# JLink-OB-072-Wiki-A1.net
KiCad netlist of a schematic drawn in Altium Designer
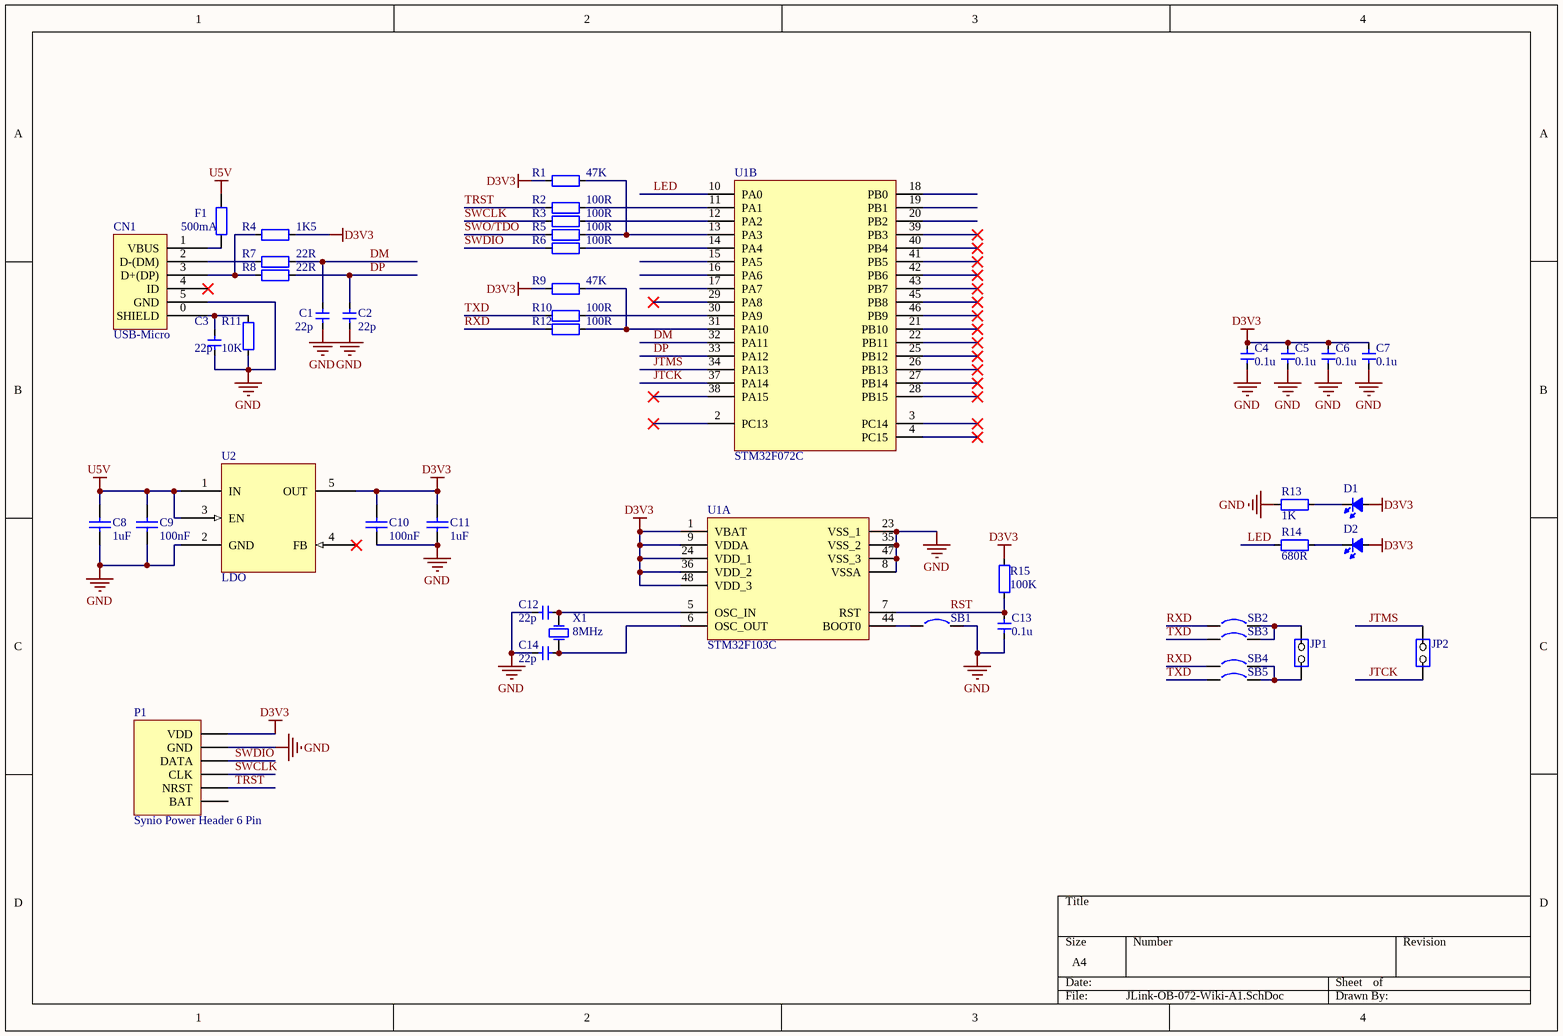
[diagram p0: JLink-OB-072-Wiki-A1.SchDoc]

(export (version "E")
  (design (tool "Eeschema 10.0.6"))
  (components
    (comp (ref "C1")
      (value "22p")
      (footprint "0603C")
      (description "Capacitor")
      (fields (field (name "Comment") "Cap_0603"))
      (libsource (lib "altium-import") (part "root_1_Cap_0603_"))
    )
    (comp (ref "C2")
      (value "22p")
      (footprint "0603C")
      (description "Capacitor")
      (fields (field (name "Comment") "Cap_0603"))
      (libsource (lib "SCH_Passive") (part "Cap_0603"))
    )
    (comp (ref "C3")
      (value "22p")
      (footprint "0603C")
      (description "Capacitor")
      (fields (field (name "Comment") "Cap_0603"))
      (libsource (lib "SCH_Passive") (part "Cap_0603"))
    )
    (comp (ref "C4")
      (value "0.1u")
      (footprint "0603C")
      (description "Capacitor")
      (fields (field (name "Comment") "Cap_0603"))
      (libsource (lib "SCH_Passive") (part "Cap_0603"))
    )
    (comp (ref "C5")
      (value "0.1u")
      (footprint "0603C")
      (description "Capacitor")
      (fields (field (name "Comment") "Cap_0603"))
      (libsource (lib "SCH_Passive") (part "Cap_0603"))
    )
    (comp (ref "C6")
      (value "0.1u")
      (footprint "0603C")
      (description "Capacitor")
      (fields (field (name "Comment") "Cap_0603"))
      (libsource (lib "SCH_Passive") (part "Cap_0603"))
    )
    (comp (ref "C7")
      (value "0.1u")
      (footprint "0603C")
      (description "Capacitor")
      (fields (field (name "Comment") "Cap_0603"))
      (libsource (lib "SCH_Passive") (part "Cap_0603"))
    )
    (comp (ref "C8")
      (value "1uF")
      (footprint "0603C")
      (description "Capacitor 0402 / 0603 / 0805")
      (libsource (lib "MCD_TOOLS") (part "Capacitor_ST"))
    )
    (comp (ref "C9")
      (value "100nF")
      (footprint "0603C")
      (description "Capacitor 0402 / 0603 / 0805")
      (libsource (lib "MCD_TOOLS") (part "Capacitor_ST"))
    )
    (comp (ref "C10")
      (value "100nF")
      (footprint "0603C")
      (description "Capacitor 0402 / 0603 / 0805")
      (libsource (lib "MCD_TOOLS") (part "Capacitor_ST"))
    )
    (comp (ref "C11")
      (value "1uF")
      (footprint "0603C")
      (description "Capacitor 0402 / 0603 / 0805")
      (libsource (lib "MCD_TOOLS") (part "Capacitor_ST"))
    )
    (comp (ref "C12")
      (value "22p")
      (footprint "0603C")
      (description "Capacitor")
      (fields (field (name "Comment") "Cap_0603"))
      (libsource (lib "SCH_Passive") (part "Cap_0603"))
    )
    (comp (ref "C13")
      (value "0.1u")
      (footprint "0603C")
      (description "Capacitor")
      (fields (field (name "Comment") "Cap_0603"))
      (libsource (lib "SCH_Passive") (part "Cap_0603"))
    )
    (comp (ref "C14")
      (value "22p")
      (footprint "0603C")
      (description "Capacitor")
      (fields (field (name "Comment") "Cap_0603"))
      (libsource (lib "SCH_Passive") (part "Cap_0603"))
    )
    (comp (ref "CN1")
      (value "USB-Micro")
      (footprint "USB_MICRO_5S_B")
      (libsource (lib "USB") (part "USB-Micro"))
    )
    (comp (ref "D1")
      (value "LED_0603")
      (footprint "LED-0603")
      (description "LED")
      (libsource (lib "SCH_Active") (part "LED_0603"))
    )
    (comp (ref "D2")
      (value "LED_0603")
      (footprint "LED-0603")
      (description "LED")
      (libsource (lib "SCH_Active") (part "LED_0603"))
    )
    (comp (ref "F1")
      (value "500mA")
      (footprint "0805M")
      (description "Resistor")
      (fields (field (name "PUBLISHER") "Altium Limited"))
      (libsource (lib "Misc") (part "Res"))
    )
    (comp (ref "JP1") (value "JP2") (footprint "HDR1X2/2.54mm") (libsource (lib "Connector") (part "JP2")))
    (comp (ref "JP2") (value "JP2") (footprint "HDR1X2/2.54mm") (libsource (lib "Connector") (part "JP2")))
    (comp (ref "P1")
      (value "Synio Power Header 6 Pin")
      (footprint "HDR1X6/2.54MM")
      (libsource (lib "Connector") (part "Synio Power Header 6 Pin"))
    )
    (comp (ref "R1")
      (value "47K")
      (footprint "0603R")
      (description "Resistor")
      (fields (field (name "Comment") "Res_0603"))
      (libsource (lib "") (part "Res_0603_1"))
    )
    (comp (ref "R2")
      (value "100R")
      (footprint "0603R")
      (description "Resistor")
      (fields (field (name "Comment") "Res_0603"))
      (libsource (lib "altium-import") (part "root_0_Res_0603_"))
    )
    (comp (ref "R3")
      (value "100R")
      (footprint "0603R")
      (description "Resistor")
      (fields (field (name "Comment") "Res_0603"))
      (libsource (lib "SCH_Passive") (part "Res_0603"))
    )
    (comp (ref "R4")
      (value "1K5")
      (footprint "0603R")
      (description "Resistor")
      (fields (field (name "Comment") "Res_0603"))
      (libsource (lib "SCH_Passive") (part "Res_0603"))
    )
    (comp (ref "R5")
      (value "100R")
      (footprint "0603R")
      (description "Resistor")
      (fields (field (name "Comment") "Res_0603"))
      (libsource (lib "SCH_Passive") (part "Res_0603"))
    )
    (comp (ref "R6")
      (value "100R")
      (footprint "0603R")
      (description "Resistor")
      (fields (field (name "Comment") "Res_0603"))
      (libsource (lib "SCH_Passive") (part "Res_0603"))
    )
    (comp (ref "R7")
      (value "22R")
      (footprint "0603R")
      (description "Resistor")
      (fields (field (name "Comment") "Res_0603"))
      (libsource (lib "SCH_Passive") (part "Res_0603"))
    )
    (comp (ref "R8")
      (value "22R")
      (footprint "0603R")
      (description "Resistor")
      (fields (field (name "Comment") "Res_0603"))
      (libsource (lib "SCH_Passive") (part "Res_0603"))
    )
    (comp (ref "R9")
      (value "47K")
      (footprint "0603R")
      (description "Resistor")
      (fields (field (name "Comment") "Res_0603"))
      (libsource (lib "") (part "Res_0603_1"))
    )
    (comp (ref "R10")
      (value "100R")
      (footprint "0603R")
      (description "Resistor")
      (fields (field (name "Comment") "Res_0603"))
      (libsource (lib "SCH_Passive") (part "Res_0603"))
    )
    (comp (ref "R11")
      (value "10K")
      (footprint "0603R")
      (description "Resistor")
      (fields (field (name "Comment") "Res_0603"))
      (libsource (lib "") (part "Res_0603_2"))
    )
    (comp (ref "R12")
      (value "100R")
      (footprint "0603R")
      (description "Resistor")
      (fields (field (name "Comment") "Res_0603"))
      (libsource (lib "SCH_Passive") (part "Res_0603"))
    )
    (comp (ref "R13")
      (value "1K")
      (footprint "0603R")
      (description "Resistor")
      (fields (field (name "Comment") "Res_0603"))
      (libsource (lib "SCH_Passive") (part "Res_0603"))
    )
    (comp (ref "R14")
      (value "680R")
      (footprint "0603R")
      (description "Resistor")
      (fields (field (name "Comment") "Res_0603"))
      (libsource (lib "SCH_Passive") (part "Res_0603"))
    )
    (comp (ref "R15")
      (value "100K")
      (footprint "0603R")
      (description "Resistor")
      (fields (field (name "Comment") "Res_0603"))
      (libsource (lib "") (part "Res_0603_2"))
    )
    (comp (ref "SB1")
      (value "Circuit Breaker")
      (footprint "JP2_SMD")
      (fields (field (name "PUBLISHER") "Altium Limited"))
      (libsource (lib "Misc") (part "Circuit Breaker"))
    )
    (comp (ref "SB2")
      (value "Circuit Breaker")
      (footprint "JP2_SMD")
      (fields (field (name "PUBLISHER") "Altium Limited"))
      (libsource (lib "Misc") (part "Circuit Breaker"))
    )
    (comp (ref "SB3")
      (value "Circuit Breaker")
      (footprint "JP2_SMD")
      (fields (field (name "PUBLISHER") "Altium Limited"))
      (libsource (lib "Misc") (part "Circuit Breaker"))
    )
    (comp (ref "SB4")
      (value "Circuit Breaker")
      (footprint "JP2_SMD")
      (fields (field (name "PUBLISHER") "Altium Limited"))
      (libsource (lib "Misc") (part "Circuit Breaker"))
    )
    (comp (ref "SB5")
      (value "Circuit Breaker")
      (footprint "JP2_SMD")
      (fields (field (name "PUBLISHER") "Altium Limited"))
      (libsource (lib "Misc") (part "Circuit Breaker"))
    )
    (comp (ref "U1")
      (value "STM32F103C")
      (footprint "LQFP48_N")
      (description "MCU")
      (libsource (lib "SCH_IC") (part "STM32F103C"))
    )
    (comp (ref "U2")
      (value "LDO")
      (footprint "SOT23-5")
      (description "General LDO SOT23-5")
      (libsource (lib "Power") (part "LDO-SOT23-5"))
    )
    (comp (ref "X1")
      (value "8MHz")
      (footprint "XTAL")
      (description "Crystal Oscillator")
      (fields (field (name "Comment") "XTAL_5032_2P"))
      (libsource (lib "SCH_Oscillator") (part "XTAL_5032_2P"))
    )
  )
  (nets
    (net (code "1") (name "/DM") (class "Default")
      (node (ref "C1") (pin "2") (pinfunction "2_2") (pintype "passive"))
      (node (ref "R7") (pin "2") (pinfunction "2_2") (pintype "passive"))
      (node (ref "U1") (pin "32") (pinfunction "PA11_32") (pintype "passive"))
    )
    (net (code "2") (name "/DP") (class "Default")
      (node (ref "C2") (pin "2") (pinfunction "2_2") (pintype "passive"))
      (node (ref "R8") (pin "2") (pinfunction "2_2") (pintype "passive"))
      (node (ref "U1") (pin "33") (pinfunction "PA12_33") (pintype "passive"))
    )
    (net (code "3") (name "/JTCK") (class "Default")
      (node (ref "JP2") (pin "1") (pinfunction "COMMON_1") (pintype "passive"))
      (node (ref "U1") (pin "37") (pinfunction "PA14_37") (pintype "passive"))
    )
    (net (code "4") (name "/JTMS") (class "Default")
      (node (ref "JP2") (pin "2") (pinfunction "NO_2") (pintype "passive"))
      (node (ref "U1") (pin "34") (pinfunction "PA13_34") (pintype "passive"))
    )
    (net (code "5") (name "/LED") (class "Default")
      (node (ref "R14") (pin "1") (pinfunction "1_1") (pintype "passive"))
      (node (ref "U1") (pin "10") (pinfunction "PA0_10") (pintype "passive"))
    )
    (net (code "6") (name "/RST") (class "Default")
      (node (ref "C13") (pin "1") (pinfunction "1_1") (pintype "passive"))
      (node (ref "R15") (pin "1") (pinfunction "1_1") (pintype "passive"))
      (node (ref "U1") (pin "7") (pinfunction "RST_7") (pintype "passive"))
    )
    (net (code "7") (name "/RXD") (class "Default")
      (node (ref "R12") (pin "1") (pinfunction "1_1") (pintype "passive"))
      (node (ref "SB2") (pin "1") (pinfunction "1_1") (pintype "passive"))
      (node (ref "SB4") (pin "1") (pinfunction "1_1") (pintype "passive"))
    )
    (net (code "8") (name "/SWCLK") (class "Default")
      (node (ref "P1") (pin "4") (pinfunction "CLK_4") (pintype "passive"))
      (node (ref "R3") (pin "1") (pinfunction "1_1") (pintype "passive"))
    )
    (net (code "9") (name "/SWDIO") (class "Default")
      (node (ref "P1") (pin "3") (pinfunction "DATA_3") (pintype "passive"))
      (node (ref "R6") (pin "1") (pinfunction "1_1") (pintype "passive"))
    )
    (net (code "10") (name "/SWO{slash}TDO") (class "Default")
      (node (ref "R5") (pin "1") (pinfunction "1_1") (pintype "passive"))
    )
    (net (code "11") (name "/TRST") (class "Default")
      (node (ref "P1") (pin "5") (pinfunction "NRST_5") (pintype "passive"))
      (node (ref "R2") (pin "1") (pinfunction "1_1") (pintype "passive"))
    )
    (net (code "12") (name "/TXD") (class "Default")
      (node (ref "R10") (pin "1") (pinfunction "1_1") (pintype "passive"))
      (node (ref "SB3") (pin "1") (pinfunction "1_1") (pintype "passive"))
      (node (ref "SB5") (pin "1") (pinfunction "1_1") (pintype "passive"))
    )
    (net (code "13") (name "D3V3") (class "Default")
      (node (ref "C10") (pin "2") (pinfunction "2_2") (pintype "passive"))
      (node (ref "C11") (pin "2") (pinfunction "2_2") (pintype "passive"))
      (node (ref "C4") (pin "1") (pinfunction "1_1") (pintype "passive"))
      (node (ref "C5") (pin "1") (pinfunction "1_1") (pintype "passive"))
      (node (ref "C6") (pin "1") (pinfunction "1_1") (pintype "passive"))
      (node (ref "C7") (pin "1") (pinfunction "1_1") (pintype "passive"))
      (node (ref "D1") (pin "1") (pinfunction "A_1") (pintype "passive"))
      (node (ref "D2") (pin "1") (pinfunction "A_1") (pintype "passive"))
      (node (ref "P1") (pin "1") (pinfunction "VDD_1") (pintype "passive"))
      (node (ref "R1") (pin "2") (pinfunction "2_2") (pintype "passive"))
      (node (ref "R15") (pin "2") (pinfunction "2_2") (pintype "passive"))
      (node (ref "R4") (pin "2") (pinfunction "2_2") (pintype "passive"))
      (node (ref "R9") (pin "2") (pinfunction "2_2") (pintype "passive"))
      (node (ref "U1") (pin "1") (pinfunction "VBAT_1") (pintype "passive"))
      (node (ref "U1") (pin "24") (pinfunction "VDD_1_24") (pintype "passive"))
      (node (ref "U1") (pin "36") (pinfunction "VDD_2_36") (pintype "passive"))
      (node (ref "U1") (pin "48") (pinfunction "VDD_3_48") (pintype "passive"))
      (node (ref "U1") (pin "9") (pinfunction "VDDA_9") (pintype "passive"))
      (node (ref "U2") (pin "5") (pinfunction "OUT_5") (pintype "power_in"))
    )
    (net (code "14") (name "GND") (class "Default")
      (node (ref "C1") (pin "1") (pinfunction "1_1") (pintype "passive"))
      (node (ref "C10") (pin "1") (pinfunction "1_1") (pintype "passive"))
      (node (ref "C11") (pin "1") (pinfunction "1_1") (pintype "passive"))
      (node (ref "C12") (pin "2") (pinfunction "2_2") (pintype "passive"))
      (node (ref "C13") (pin "2") (pinfunction "2_2") (pintype "passive"))
      (node (ref "C14") (pin "2") (pinfunction "2_2") (pintype "passive"))
      (node (ref "C2") (pin "1") (pinfunction "1_1") (pintype "passive"))
      (node (ref "C3") (pin "1") (pinfunction "1_1") (pintype "passive"))
      (node (ref "C4") (pin "2") (pinfunction "2_2") (pintype "passive"))
      (node (ref "C5") (pin "2") (pinfunction "2_2") (pintype "passive"))
      (node (ref "C6") (pin "2") (pinfunction "2_2") (pintype "passive"))
      (node (ref "C7") (pin "2") (pinfunction "2_2") (pintype "passive"))
      (node (ref "C8") (pin "1") (pinfunction "1_1") (pintype "passive"))
      (node (ref "C9") (pin "1") (pinfunction "1_1") (pintype "passive"))
      (node (ref "CN1") (pin "5") (pinfunction "GND_5") (pintype "passive"))
      (node (ref "P1") (pin "2") (pinfunction "GND_2") (pintype "passive"))
      (node (ref "R11") (pin "1") (pinfunction "1_1") (pintype "passive"))
      (node (ref "R13") (pin "1") (pinfunction "1_1") (pintype "passive"))
      (node (ref "SB1") (pin "2") (pinfunction "2_2") (pintype "passive"))
      (node (ref "U1") (pin "23") (pinfunction "VSS_1_23") (pintype "passive"))
      (node (ref "U1") (pin "35") (pinfunction "VSS_2_35") (pintype "passive"))
      (node (ref "U1") (pin "47") (pinfunction "VSS_3_47") (pintype "passive"))
      (node (ref "U1") (pin "8") (pinfunction "VSSA_8") (pintype "passive"))
      (node (ref "U2") (pin "2") (pinfunction "GND_2") (pintype "power_in"))
    )
    (net (code "15") (name "Net-(CN1-D+(DP))") (class "Default")
      (node (ref "CN1") (pin "3") (pinfunction "D+(DP)_3") (pintype "passive"))
      (node (ref "R4") (pin "1") (pinfunction "1_1") (pintype "passive"))
      (node (ref "R8") (pin "1") (pinfunction "1_1") (pintype "passive"))
    )
    (net (code "16") (name "Net-(CN1-D-(DM))") (class "Default")
      (node (ref "CN1") (pin "2") (pinfunction "D-(DM)_2") (pintype "passive"))
      (node (ref "R7") (pin "1") (pinfunction "1_1") (pintype "passive"))
    )
    (net (code "17") (name "Net-(CN1-SHIELD)") (class "Default")
      (node (ref "C3") (pin "2") (pinfunction "2_2") (pintype "passive"))
      (node (ref "CN1") (pin "0") (pinfunction "SHIELD_0") (pintype "passive"))
      (node (ref "R11") (pin "2") (pinfunction "2_2") (pintype "passive"))
    )
    (net (code "18") (name "Net-(CN1-VBUS)") (class "Default")
      (node (ref "CN1") (pin "1") (pinfunction "VBUS_1") (pintype "passive"))
      (node (ref "F1") (pin "1") (pinfunction "1_1") (pintype "passive"))
    )
    (net (code "19") (name "Net-(D1-K)") (class "Default")
      (node (ref "D1") (pin "2") (pinfunction "K_2") (pintype "passive"))
      (node (ref "R13") (pin "2") (pinfunction "2_2") (pintype "passive"))
    )
    (net (code "20") (name "Net-(D2-K)") (class "Default")
      (node (ref "D2") (pin "2") (pinfunction "K_2") (pintype "passive"))
      (node (ref "R14") (pin "2") (pinfunction "2_2") (pintype "passive"))
    )
    (net (code "21") (name "Net-(JP1-COMMON)") (class "Default")
      (node (ref "JP1") (pin "1") (pinfunction "COMMON_1") (pintype "passive"))
      (node (ref "SB4") (pin "2") (pinfunction "2_2") (pintype "passive"))
      (node (ref "SB5") (pin "2") (pinfunction "2_2") (pintype "passive"))
    )
    (net (code "22") (name "Net-(JP1-NO)") (class "Default")
      (node (ref "JP1") (pin "2") (pinfunction "NO_2") (pintype "passive"))
      (node (ref "SB2") (pin "2") (pinfunction "2_2") (pintype "passive"))
      (node (ref "SB3") (pin "2") (pinfunction "2_2") (pintype "passive"))
    )
    (net (code "23") (name "Net-(U1A-BOOT0)") (class "Default")
      (node (ref "SB1") (pin "1") (pinfunction "1_1") (pintype "passive"))
      (node (ref "U1") (pin "44") (pinfunction "BOOT0_44") (pintype "passive"))
    )
    (net (code "24") (name "Net-(U1A-OSC_IN)") (class "Default")
      (node (ref "C12") (pin "1") (pinfunction "1_1") (pintype "passive"))
      (node (ref "U1") (pin "5") (pinfunction "OSC_IN_5") (pintype "passive"))
      (node (ref "X1") (pin "2") (pinfunction "OSC2_2") (pintype "passive"))
    )
    (net (code "25") (name "Net-(U1A-OSC_OUT)") (class "Default")
      (node (ref "C14") (pin "1") (pinfunction "1_1") (pintype "passive"))
      (node (ref "U1") (pin "6") (pinfunction "OSC_OUT_6") (pintype "passive"))
      (node (ref "X1") (pin "1") (pinfunction "OSC1_1") (pintype "passive"))
    )
    (net (code "26") (name "Net-(U1B-PA1)") (class "Default")
      (node (ref "R2") (pin "2") (pinfunction "2_2") (pintype "passive"))
      (node (ref "U1") (pin "11") (pinfunction "PA1_11") (pintype "passive"))
    )
    (net (code "27") (name "Net-(U1B-PA2)") (class "Default")
      (node (ref "R3") (pin "2") (pinfunction "2_2") (pintype "passive"))
      (node (ref "U1") (pin "12") (pinfunction "PA2_12") (pintype "passive"))
    )
    (net (code "28") (name "Net-(U1B-PA3)") (class "Default")
      (node (ref "R1") (pin "1") (pinfunction "1_1") (pintype "passive"))
      (node (ref "R5") (pin "2") (pinfunction "2_2") (pintype "passive"))
      (node (ref "U1") (pin "13") (pinfunction "PA3_13") (pintype "passive"))
    )
    (net (code "29") (name "Net-(U1B-PA4)") (class "Default")
      (node (ref "R6") (pin "2") (pinfunction "2_2") (pintype "passive"))
      (node (ref "U1") (pin "14") (pinfunction "PA4_14") (pintype "passive"))
    )
    (net (code "30") (name "Net-(U1B-PA9)") (class "Default")
      (node (ref "R10") (pin "2") (pinfunction "2_2") (pintype "passive"))
      (node (ref "U1") (pin "30") (pinfunction "PA9_30") (pintype "passive"))
    )
    (net (code "31") (name "Net-(U1B-PA10)") (class "Default")
      (node (ref "R12") (pin "2") (pinfunction "2_2") (pintype "passive"))
      (node (ref "R9") (pin "1") (pinfunction "1_1") (pintype "passive"))
      (node (ref "U1") (pin "31") (pinfunction "PA10_31") (pintype "passive"))
    )
    (net (code "32") (name "U5V") (class "Default")
      (node (ref "C8") (pin "2") (pinfunction "2_2") (pintype "passive"))
      (node (ref "C9") (pin "2") (pinfunction "2_2") (pintype "passive"))
      (node (ref "F1") (pin "2") (pinfunction "2_2") (pintype "passive"))
      (node (ref "U2") (pin "1") (pinfunction "IN_1") (pintype "power_in"))
      (node (ref "U2") (pin "3") (pinfunction "EN_3") (pintype "input"))
    )
    (net (code "33") (name "unconnected-(CN1-ID-Pad4)") (class "Default")
      (node (ref "CN1") (pin "4") (pinfunction "ID_4") (pintype "passive+no_connect"))
    )
    (net (code "34") (name "unconnected-(P1-BAT-Pad6)") (class "Default")
      (node (ref "P1") (pin "6") (pinfunction "BAT_6") (pintype "passive"))
    )
    (net (code "35") (name "unconnected-(U1B-PA5-Pad15)") (class "Default")
      (node (ref "U1") (pin "15") (pinfunction "PA5_15") (pintype "passive"))
    )
    (net (code "36") (name "unconnected-(U1B-PA6-Pad16)") (class "Default")
      (node (ref "U1") (pin "16") (pinfunction "PA6_16") (pintype "passive"))
    )
    (net (code "37") (name "unconnected-(U1B-PA7-Pad17)") (class "Default")
      (node (ref "U1") (pin "17") (pinfunction "PA7_17") (pintype "passive"))
    )
    (net (code "38") (name "unconnected-(U1B-PA8-Pad29)") (class "Default")
      (node (ref "U1") (pin "29") (pinfunction "PA8_29") (pintype "passive+no_connect"))
    )
    (net (code "39") (name "unconnected-(U1B-PA15-Pad38)") (class "Default")
      (node (ref "U1") (pin "38") (pinfunction "PA15_38") (pintype "passive+no_connect"))
    )
    (net (code "40") (name "unconnected-(U1B-PB0-Pad18)") (class "Default")
      (node (ref "U1") (pin "18") (pinfunction "PB0_18") (pintype "passive"))
    )
    (net (code "41") (name "unconnected-(U1B-PB1-Pad19)") (class "Default")
      (node (ref "U1") (pin "19") (pinfunction "PB1_19") (pintype "passive"))
    )
    (net (code "42") (name "unconnected-(U1B-PB2-Pad20)") (class "Default")
      (node (ref "U1") (pin "20") (pinfunction "PB2_20") (pintype "passive"))
    )
    (net (code "43") (name "unconnected-(U1B-PB3-Pad39)") (class "Default")
      (node (ref "U1") (pin "39") (pinfunction "PB3_39") (pintype "passive+no_connect"))
    )
    (net (code "44") (name "unconnected-(U1B-PB4-Pad40)") (class "Default")
      (node (ref "U1") (pin "40") (pinfunction "PB4_40") (pintype "passive+no_connect"))
    )
    (net (code "45") (name "unconnected-(U1B-PB5-Pad41)") (class "Default")
      (node (ref "U1") (pin "41") (pinfunction "PB5_41") (pintype "passive+no_connect"))
    )
    (net (code "46") (name "unconnected-(U1B-PB6-Pad42)") (class "Default")
      (node (ref "U1") (pin "42") (pinfunction "PB6_42") (pintype "passive+no_connect"))
    )
    (net (code "47") (name "unconnected-(U1B-PB7-Pad43)") (class "Default")
      (node (ref "U1") (pin "43") (pinfunction "PB7_43") (pintype "passive+no_connect"))
    )
    (net (code "48") (name "unconnected-(U1B-PB8-Pad45)") (class "Default")
      (node (ref "U1") (pin "45") (pinfunction "PB8_45") (pintype "passive+no_connect"))
    )
    (net (code "49") (name "unconnected-(U1B-PB9-Pad46)") (class "Default")
      (node (ref "U1") (pin "46") (pinfunction "PB9_46") (pintype "passive+no_connect"))
    )
    (net (code "50") (name "unconnected-(U1B-PB10-Pad21)") (class "Default")
      (node (ref "U1") (pin "21") (pinfunction "PB10_21") (pintype "passive+no_connect"))
    )
    (net (code "51") (name "unconnected-(U1B-PB11-Pad22)") (class "Default")
      (node (ref "U1") (pin "22") (pinfunction "PB11_22") (pintype "passive+no_connect"))
    )
    (net (code "52") (name "unconnected-(U1B-PB12-Pad25)") (class "Default")
      (node (ref "U1") (pin "25") (pinfunction "PB12_25") (pintype "passive+no_connect"))
    )
    (net (code "53") (name "unconnected-(U1B-PB13-Pad26)") (class "Default")
      (node (ref "U1") (pin "26") (pinfunction "PB13_26") (pintype "passive+no_connect"))
    )
    (net (code "54") (name "unconnected-(U1B-PB14-Pad27)") (class "Default")
      (node (ref "U1") (pin "27") (pinfunction "PB14_27") (pintype "passive+no_connect"))
    )
    (net (code "55") (name "unconnected-(U1B-PB15-Pad28)") (class "Default")
      (node (ref "U1") (pin "28") (pinfunction "PB15_28") (pintype "passive+no_connect"))
    )
    (net (code "56") (name "unconnected-(U1B-PC13-Pad2)") (class "Default")
      (node (ref "U1") (pin "2") (pinfunction "PC13_2") (pintype "passive+no_connect"))
    )
    (net (code "57") (name "unconnected-(U1B-PC14-Pad3)") (class "Default")
      (node (ref "U1") (pin "3") (pinfunction "PC14_3") (pintype "passive+no_connect"))
    )
    (net (code "58") (name "unconnected-(U1B-PC15-Pad4)") (class "Default")
      (node (ref "U1") (pin "4") (pinfunction "PC15_4") (pintype "passive+no_connect"))
    )
    (net (code "59") (name "unconnected-(U2-FB-Pad4)") (class "Default")
      (node (ref "U2") (pin "4") (pinfunction "FB_4") (pintype "input+no_connect"))
    )
  )
)
